# UKU207xx_power_board.net
KiCad netlist of a schematic drawn in Altium Designer
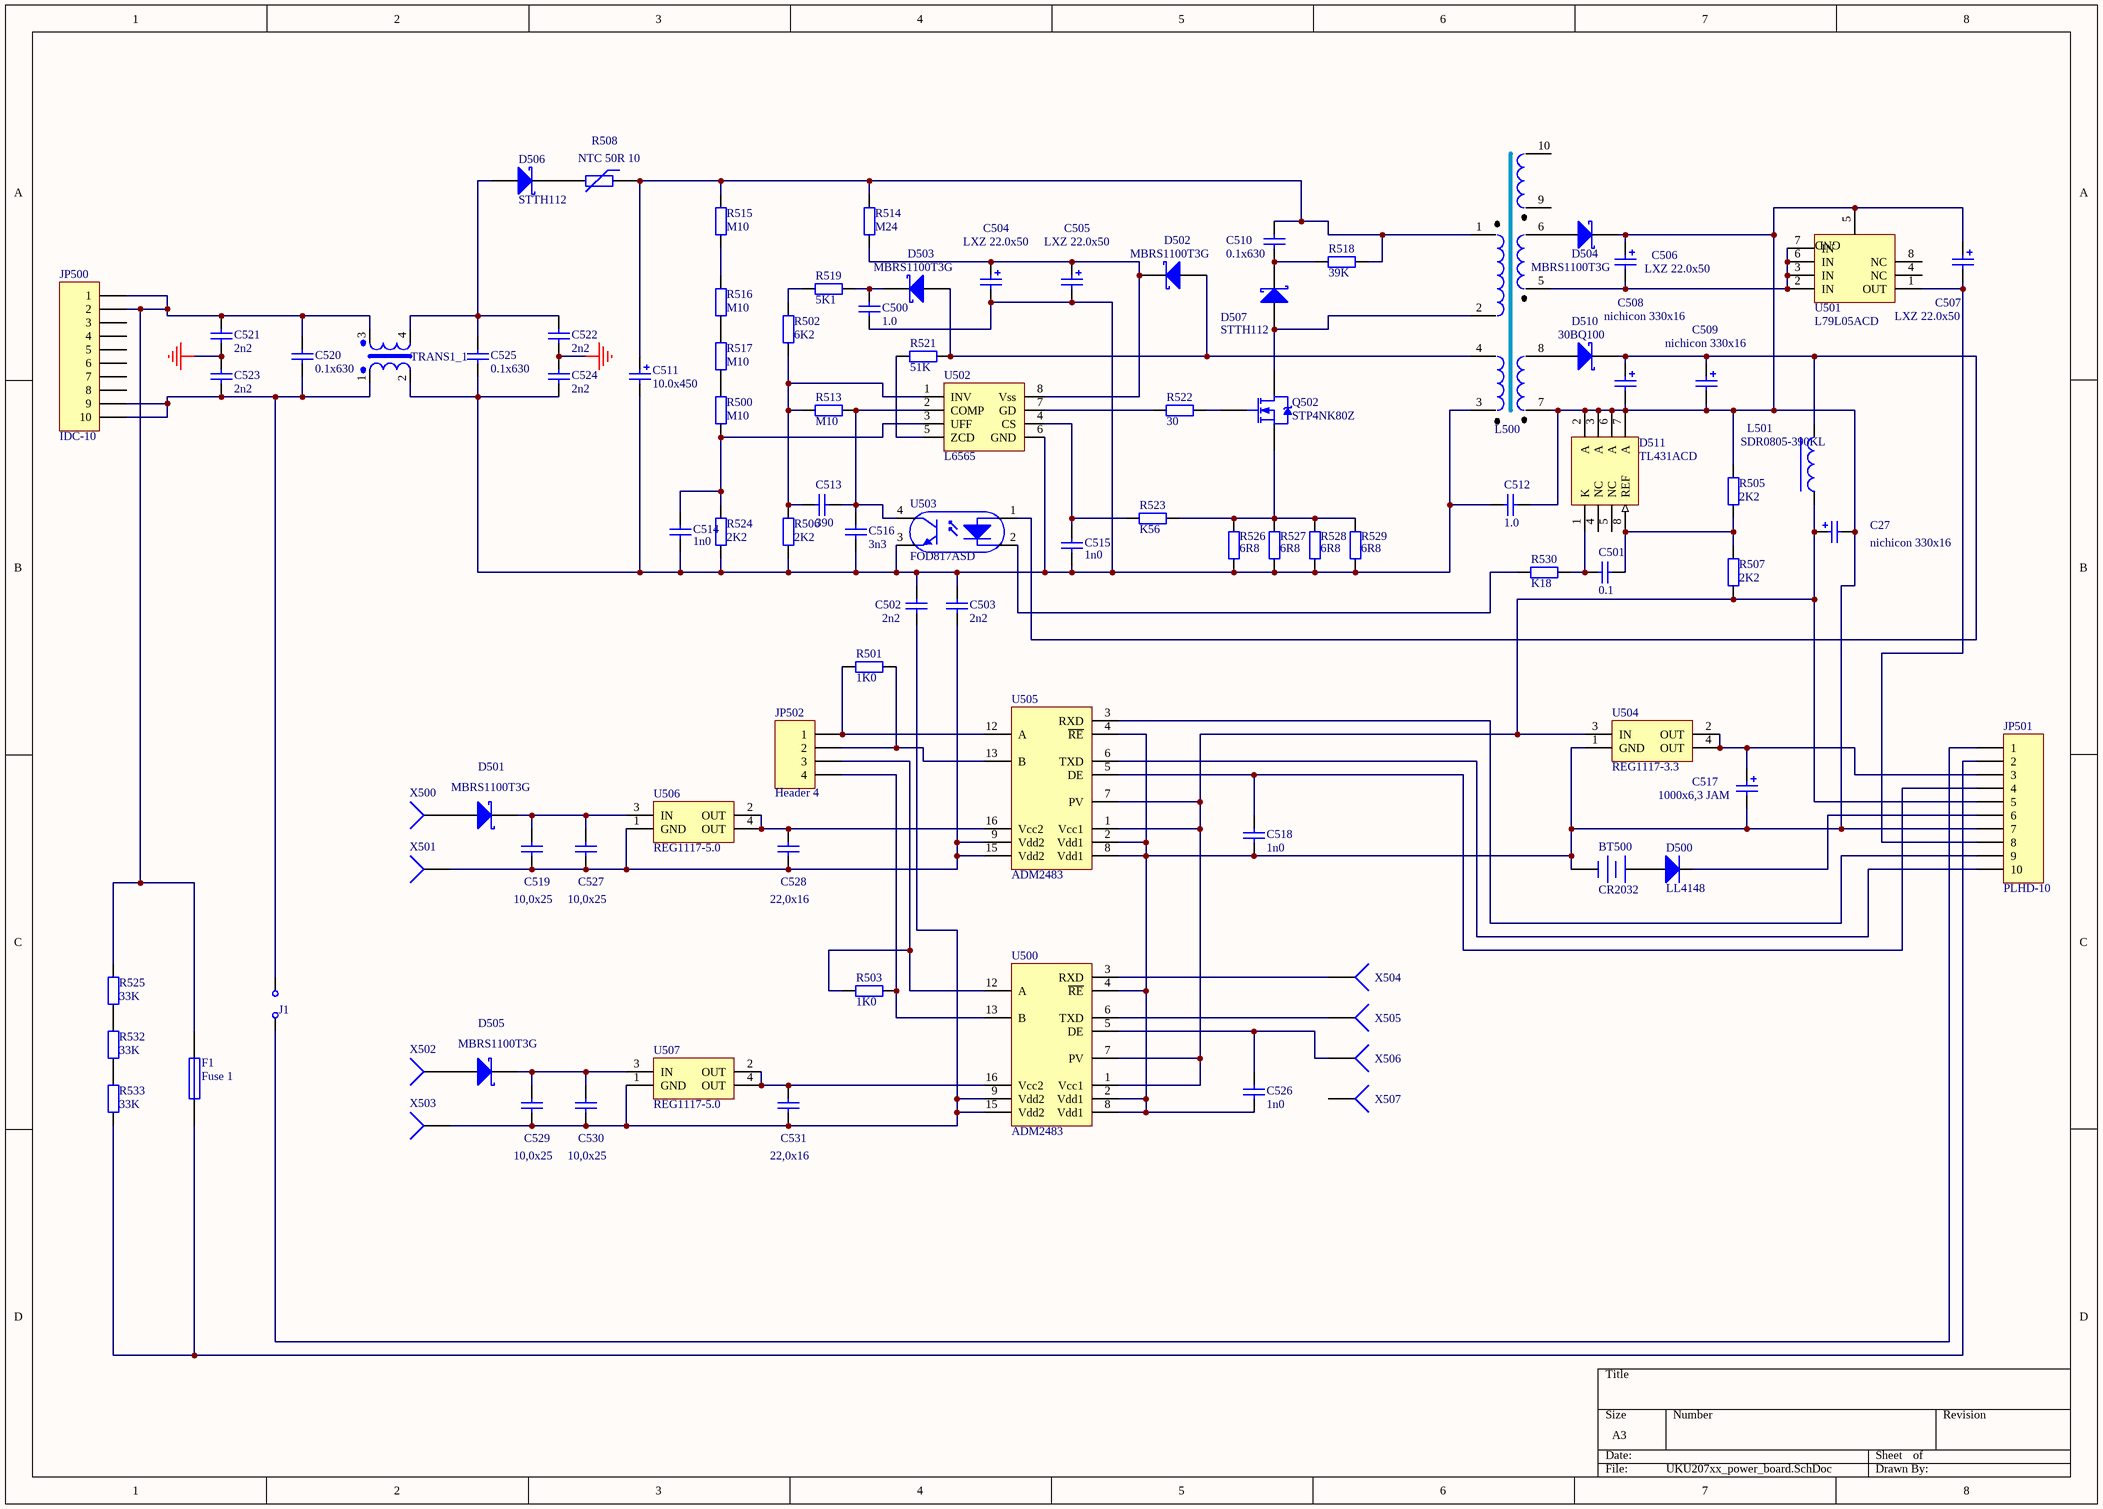
[diagram p0: UKU207xx_power_board.SchDoc]

(export (version "E")
  (design (tool "Eeschema 10.0.6"))
  (components
    (comp (ref "BT500")
      (value "CR2032")
      (footprint "BAT_HOLD_SMD")
      (description "Multicell Battery")
      (fields (field (name "MANUFACTURER") "Generic Components") (field (name "PUBLISHER") "Altium Limited"))
      (libsource (lib "Miscellaneous Devices") (part "Battery"))
    )
    (comp (ref "C27")
      (value "nichicon 330x16")
      (footprint "el3")
      (description "Polarized Capacitor (Radial)")
      (fields (field (name "MANUFACTURER") "Generic Components") (field (name "PUBLISHER") "Altium Limited"))
      (libsource (lib "PAL") (part "Cap Pol1"))
    )
    (comp (ref "C500")
      (value "1.0")
      (footprint "_1206")
      (description "Capacitor (Semiconductor SIM Model)")
      (fields (field (name "MANUFACTURER") "Generic Components") (field (name "PUBLISHER") "Altium Limited"))
      (libsource (lib "Miscellaneous Devices") (part "Cap Semi"))
    )
    (comp (ref "C501")
      (value "0.1")
      (footprint "_1206")
      (description "Capacitor (Semiconductor SIM Model)")
      (fields (field (name "MANUFACTURER") "Generic Components") (field (name "PUBLISHER") "Altium Limited"))
      (libsource (lib "Miscellaneous Devices") (part "Cap Semi"))
    )
    (comp (ref "C502")
      (value "2n2")
      (footprint "C8")
      (description "Capacitor (Semiconductor SIM Model)")
      (fields (field (name "MANUFACTURER") "Generic Components") (field (name "PUBLISHER") "Altium Limited"))
      (libsource (lib "Miscellaneous Devices") (part "Cap Semi"))
    )
    (comp (ref "C503")
      (value "2n2")
      (footprint "C8")
      (description "Capacitor (Semiconductor SIM Model)")
      (fields (field (name "MANUFACTURER") "Generic Components") (field (name "PUBLISHER") "Altium Limited"))
      (libsource (lib "Miscellaneous Devices") (part "Cap Semi"))
    )
    (comp (ref "C504")
      (value "LXZ 22.0x50")
      (footprint "el3")
      (description "Polarized Capacitor (Radial)")
      (fields (field (name "MANUFACTURER") "Generic Components") (field (name "PUBLISHER") "Altium Limited"))
      (libsource (lib "PAL") (part "Cap Pol1"))
    )
    (comp (ref "C505")
      (value "LXZ 22.0x50")
      (footprint "el3")
      (description "Polarized Capacitor (Radial)")
      (fields (field (name "MANUFACTURER") "Generic Components") (field (name "PUBLISHER") "Altium Limited"))
      (libsource (lib "PAL") (part "Cap Pol1"))
    )
    (comp (ref "C506")
      (value "LXZ 22.0x50")
      (footprint "el3")
      (description "Polarized Capacitor (Radial)")
      (fields (field (name "MANUFACTURER") "Generic Components") (field (name "PUBLISHER") "Altium Limited"))
      (libsource (lib "PAL") (part "Cap Pol1"))
    )
    (comp (ref "C507")
      (value "LXZ 22.0x50")
      (footprint "el3")
      (description "Polarized Capacitor (Radial)")
      (fields (field (name "MANUFACTURER") "Generic Components") (field (name "PUBLISHER") "Altium Limited"))
      (libsource (lib "PAL") (part "Cap Pol1"))
    )
    (comp (ref "C508")
      (value "nichicon 330x16")
      (footprint "el3")
      (description "Polarized Capacitor (Radial)")
      (fields (field (name "MANUFACTURER") "Generic Components") (field (name "PUBLISHER") "Altium Limited"))
      (libsource (lib "PAL") (part "Cap Pol1"))
    )
    (comp (ref "C509")
      (value "nichicon 330x16")
      (footprint "el3")
      (description "Polarized Capacitor (Radial)")
      (fields (field (name "MANUFACTURER") "Generic Components") (field (name "PUBLISHER") "Altium Limited"))
      (libsource (lib "PAL") (part "Cap Pol1"))
    )
    (comp (ref "C510")
      (value "0.1x630")
      (footprint "c15")
      (description "Capacitor (Semiconductor SIM Model)")
      (fields (field (name "MANUFACTURER") "Generic Components") (field (name "PUBLISHER") "Altium Limited"))
      (libsource (lib "Miscellaneous Devices") (part "Cap Semi"))
    )
    (comp (ref "C511")
      (value "10.0x450")
      (footprint "el_15_25_h")
      (description "Polarized Capacitor (Radial)")
      (fields (field (name "MANUFACTURER") "Generic Components") (field (name "PUBLISHER") "Altium Limited"))
      (libsource (lib "PAL") (part "Cap Pol1"))
    )
    (comp (ref "C512")
      (value "1.0")
      (footprint "C8")
      (description "Capacitor (Semiconductor SIM Model)")
      (fields (field (name "MANUFACTURER") "Generic Components") (field (name "PUBLISHER") "Altium Limited"))
      (libsource (lib "Miscellaneous Devices") (part "Cap Semi"))
    )
    (comp (ref "C513")
      (value "390")
      (footprint "_1206")
      (description "Capacitor (Semiconductor SIM Model)")
      (fields (field (name "MANUFACTURER") "Generic Components") (field (name "PUBLISHER") "Altium Limited"))
      (libsource (lib "Miscellaneous Devices") (part "Cap Semi"))
    )
    (comp (ref "C514")
      (value "1n0")
      (footprint "_1206")
      (description "Capacitor (Semiconductor SIM Model)")
      (fields (field (name "MANUFACTURER") "Generic Components") (field (name "PUBLISHER") "Altium Limited"))
      (libsource (lib "Miscellaneous Devices") (part "Cap Semi"))
    )
    (comp (ref "C515")
      (value "1n0")
      (footprint "_1206")
      (description "Capacitor (Semiconductor SIM Model)")
      (fields (field (name "MANUFACTURER") "Generic Components") (field (name "PUBLISHER") "Altium Limited"))
      (libsource (lib "Miscellaneous Devices") (part "Cap Semi"))
    )
    (comp (ref "C516")
      (value "3n3")
      (footprint "_1206")
      (description "Capacitor (Semiconductor SIM Model)")
      (fields (field (name "MANUFACTURER") "Generic Components") (field (name "PUBLISHER") "Altium Limited"))
      (libsource (lib "Miscellaneous Devices") (part "Cap Semi"))
    )
    (comp (ref "C517")
      (value "1000x6,3 JAM")
      (footprint "el5")
      (description "Polarized Capacitor (Radial)")
      (fields (field (name "MANUFACTURER") "Generic Components") (field (name "PUBLISHER") "Altium Limited"))
      (libsource (lib "PAL") (part "Cap Pol1"))
    )
    (comp (ref "C518")
      (value "1n0")
      (footprint "_1206")
      (description "Capacitor (Semiconductor SIM Model)")
      (fields (field (name "MANUFACTURER") "Generic Components") (field (name "PUBLISHER") "Altium Limited"))
      (libsource (lib "Miscellaneous Devices") (part "Cap Semi"))
    )
    (comp (ref "C519")
      (value "1.0")
      (footprint "_1206")
      (description "Capacitor (Semiconductor SIM Model)")
      (fields
        (field (name "MANUFACTURER") "Generic Components")
        (field (name "ALTIUM_VALUE") "10,0x25")
        (field (name "PUBLISHER") "Altium Limited")
      )
      (libsource (lib "Miscellaneous Devices") (part "Cap Semi"))
    )
    (comp (ref "C520")
      (value "0.1x630")
      (footprint "c15")
      (description "Capacitor (Semiconductor SIM Model)")
      (fields (field (name "MANUFACTURER") "Generic Components") (field (name "PUBLISHER") "Altium Limited"))
      (libsource (lib "Miscellaneous Devices") (part "Cap Semi"))
    )
    (comp (ref "C521")
      (value "2n2")
      (footprint "C8")
      (description "Capacitor (Semiconductor SIM Model)")
      (fields (field (name "MANUFACTURER") "Generic Components") (field (name "PUBLISHER") "Altium Limited"))
      (libsource (lib "Miscellaneous Devices") (part "Cap Semi"))
    )
    (comp (ref "C522")
      (value "2n2")
      (footprint "c8")
      (description "Capacitor (Semiconductor SIM Model)")
      (fields (field (name "MANUFACTURER") "Generic Components") (field (name "PUBLISHER") "Altium Limited"))
      (libsource (lib "Miscellaneous Devices") (part "Cap Semi"))
    )
    (comp (ref "C523")
      (value "2n2")
      (footprint "c8")
      (description "Capacitor (Semiconductor SIM Model)")
      (fields (field (name "MANUFACTURER") "Generic Components") (field (name "PUBLISHER") "Altium Limited"))
      (libsource (lib "Miscellaneous Devices") (part "Cap Semi"))
    )
    (comp (ref "C524")
      (value "2n2")
      (footprint "c8")
      (description "Capacitor (Semiconductor SIM Model)")
      (fields (field (name "MANUFACTURER") "Generic Components") (field (name "PUBLISHER") "Altium Limited"))
      (libsource (lib "Miscellaneous Devices") (part "Cap Semi"))
    )
    (comp (ref "C525")
      (value "0.1х630")
      (footprint "c15")
      (description "Capacitor (Semiconductor SIM Model)")
      (fields (field (name "MANUFACTURER") "Generic Components") (field (name "PUBLISHER") "Altium Limited"))
      (libsource (lib "Miscellaneous Devices") (part "Cap Semi"))
    )
    (comp (ref "C526")
      (value "1n0")
      (footprint "_1206")
      (description "Capacitor (Semiconductor SIM Model)")
      (fields (field (name "MANUFACTURER") "Generic Components") (field (name "PUBLISHER") "Altium Limited"))
      (libsource (lib "Miscellaneous Devices") (part "Cap Semi"))
    )
    (comp (ref "C527")
      (value "1.0")
      (footprint "_1206")
      (description "Capacitor (Semiconductor SIM Model)")
      (fields
        (field (name "MANUFACTURER") "Generic Components")
        (field (name "ALTIUM_VALUE") "10,0x25")
        (field (name "PUBLISHER") "Altium Limited")
      )
      (libsource (lib "Miscellaneous Devices") (part "Cap Semi"))
    )
    (comp (ref "C528")
      (value "1.0")
      (footprint "_1206")
      (description "Capacitor (Semiconductor SIM Model)")
      (fields
        (field (name "MANUFACTURER") "Generic Components")
        (field (name "ALTIUM_VALUE") "22,0x16")
        (field (name "PUBLISHER") "Altium Limited")
      )
      (libsource (lib "Miscellaneous Devices") (part "Cap Semi"))
    )
    (comp (ref "C529")
      (value "1.0")
      (footprint "_1206")
      (description "Capacitor (Semiconductor SIM Model)")
      (fields
        (field (name "MANUFACTURER") "Generic Components")
        (field (name "ALTIUM_VALUE") "10,0x25")
        (field (name "PUBLISHER") "Altium Limited")
      )
      (libsource (lib "Miscellaneous Devices") (part "Cap Semi"))
    )
    (comp (ref "C530")
      (value "1.0")
      (footprint "_1206")
      (description "Capacitor (Semiconductor SIM Model)")
      (fields
        (field (name "MANUFACTURER") "Generic Components")
        (field (name "ALTIUM_VALUE") "10,0x25")
        (field (name "PUBLISHER") "Altium Limited")
      )
      (libsource (lib "Miscellaneous Devices") (part "Cap Semi"))
    )
    (comp (ref "C531")
      (value "1.0")
      (footprint "_1206")
      (description "Capacitor (Semiconductor SIM Model)")
      (fields
        (field (name "MANUFACTURER") "Generic Components")
        (field (name "ALTIUM_VALUE") "22,0x16")
        (field (name "PUBLISHER") "Altium Limited")
      )
      (libsource (lib "Miscellaneous Devices") (part "Cap Semi"))
    )
    (comp (ref "D500")
      (value "LL4148")
      (footprint "_1206d")
      (description "Default Diode")
      (fields (field (name "MANUFACTURER") "Generic Components") (field (name "PUBLISHER") "Altium Limited"))
      (libsource (lib "PAL") (part "Diode"))
    )
    (comp (ref "D501")
      (value "MBRS1100T3G")
      (footprint "D_6_3")
      (description "Schottky Rectifier")
      (fields
        (field (name "MANUFACTURER") "International Rectifier")
        (field (name "PUBLISHER") "Altium Limited")
      )
      (libsource (lib "IR Discrete Diode") (part "10BQ015"))
    )
    (comp (ref "D502")
      (value "MBRS1100T3G")
      (footprint "D_6_3")
      (description "Schottky Rectifier")
      (fields
        (field (name "MANUFACTURER") "International Rectifier")
        (field (name "PUBLISHER") "Altium Limited")
      )
      (libsource (lib "IR Discrete Diode") (part "10BQ015"))
    )
    (comp (ref "D503")
      (value "MBRS1100T3G")
      (footprint "D_6_3")
      (description "Schottky Rectifier")
      (fields
        (field (name "MANUFACTURER") "International Rectifier")
        (field (name "PUBLISHER") "Altium Limited")
      )
      (libsource (lib "IR Discrete Diode") (part "10BQ015"))
    )
    (comp (ref "D504")
      (value "MBRS1100T3G")
      (footprint "D_6_3")
      (description "Schottky Rectifier")
      (fields
        (field (name "MANUFACTURER") "International Rectifier")
        (field (name "PUBLISHER") "Altium Limited")
      )
      (libsource (lib "IR Discrete Diode") (part "10BQ015"))
    )
    (comp (ref "D505")
      (value "MBRS1100T3G")
      (footprint "D_6_3")
      (description "Schottky Rectifier")
      (fields
        (field (name "MANUFACTURER") "International Rectifier")
        (field (name "PUBLISHER") "Altium Limited")
      )
      (libsource (lib "IR Discrete Diode") (part "10BQ015"))
    )
    (comp (ref "D506")
      (value "STTH112")
      (footprint "D_6_3")
      (description "Schottky Diode")
      (fields
        (field (name "MANUFACTURER") "International Rectifier")
        (field (name "PUBLISHER") "Altium Limited")
      )
      (libsource (lib "IR Discrete Diode") (part "10BQ015"))
    )
    (comp (ref "D507")
      (value "STTH112")
      (footprint "D_6_3")
      (description "Schottky Diode")
      (fields
        (field (name "MANUFACTURER") "International Rectifier")
        (field (name "PUBLISHER") "Altium Limited")
      )
      (libsource (lib "IR Discrete Diode") (part "10BQ015"))
    )
    (comp (ref "D510")
      (value "30BQ100")
      (footprint "30BQ100")
      (description "Schottky Rectifier")
      (fields
        (field (name "MANUFACTURER") "International Rectifier")
        (field (name "PUBLISHER") "Altium Limited")
      )
      (libsource (lib "IR Discrete Diode") (part "10BQ015"))
    )
    (comp (ref "D511")
      (value "TL431ACD")
      (footprint "SO-G8")
      (description "Programmable Precision Reference")
      (fields (field (name "MANUFACTURER") "Motorola") (field (name "PUBLISHER") "Altium Limited"))
      (libsource (lib "Motorola Power Management Voltage Reference") (part "TL431ACD"))
    )
    (comp (ref "F1")
      (value "Fuse 1")
      (footprint "PIN-W2/E2.8")
      (description "Fuse")
      (fields (field (name "MANUFACTURER") "Generic Components") (field (name "PUBLISHER") "Altium Limited"))
      (libsource (lib "Miscellaneous Devices") (part "Fuse 1"))
    )
    (comp (ref "J1")
      (value "~")
      (footprint "BT5-2")
      (description "Switch")
      (fields (field (name "MANUFACTURER") "Generic Components") (field (name "PUBLISHER") "Altium Limited"))
      (libsource (lib "PAL") (part "JMP"))
    )
    (comp (ref "JP500")
      (value "IDC-10")
      (footprint "HDR2X5")
      (description "Header, 10-Pin")
      (fields (field (name "MANUFACTURER") "Generic Components") (field (name "PUBLISHER") "Altium Limited"))
      (libsource (lib "") (part "Header 10_1"))
    )
    (comp (ref "JP501")
      (value "PLHD-10")
      (footprint "HDR2X5")
      (description "Header, 10-Pin")
      (fields (field (name "MANUFACTURER") "Generic Components") (field (name "PUBLISHER") "Altium Limited"))
      (libsource (lib "Miscellaneous Connectors") (part "Header 10"))
    )
    (comp (ref "JP502")
      (value "Header 4")
      (footprint "PAL:2EDG-5.08-4")
      (description "Header, 4-Pin")
      (fields (field (name "MANUFACTURER") "Generic Components") (field (name "PUBLISHER") "Altium Limited"))
      (libsource (lib "Miscellaneous Connectors") (part "Header 4"))
    )
    (comp (ref "L500")
      (value "L220-K10")
      (footprint "trans_ring1")
      (description "Дроссель")
      (libsource (lib "PAL") (part "L1_dc_2"))
    )
    (comp (ref "L501")
      (value "SDR0805-390KL")
      (footprint "L10x10")
      (description "Magnetic-Core Inductor")
      (fields (field (name "MANUFACTURER") "Generic Components") (field (name "PUBLISHER") "Altium Limited"))
      (libsource (lib "PAL") (part "Inductor Konstr 2"))
    )
    (comp (ref "Q502")
      (value "STP4NK80Z")
      (footprint "TO220_h")
      (description "N-Channel Power MOSFET")
      (fields (field (name "MANUFACTURER") "Generic Components") (field (name "PUBLISHER") "Altium Limited"))
      (libsource (lib "Miscellaneous Devices") (part "NMOS-2"))
    )
    (comp (ref "R500")
      (value "M10")
      (footprint "_1206")
      (description "Resistor")
      (fields (field (name "MANUFACTURER") "Generic Components") (field (name "PUBLISHER") "Altium Limited"))
      (libsource (lib "Miscellaneous Devices") (part "Res2"))
    )
    (comp (ref "R501")
      (value "1K0")
      (footprint "_1206")
      (description "Resistor")
      (fields (field (name "MANUFACTURER") "Generic Components") (field (name "PUBLISHER") "Altium Limited"))
      (libsource (lib "") (part "Res2_2"))
    )
    (comp (ref "R502")
      (value "6K2")
      (footprint "_1206")
      (description "Resistor")
      (fields (field (name "MANUFACTURER") "Generic Components") (field (name "PUBLISHER") "Altium Limited"))
      (libsource (lib "Miscellaneous Devices") (part "Res2"))
    )
    (comp (ref "R503")
      (value "1K0")
      (footprint "_1206")
      (description "Resistor")
      (fields (field (name "MANUFACTURER") "Generic Components") (field (name "PUBLISHER") "Altium Limited"))
      (libsource (lib "") (part "Res2_2"))
    )
    (comp (ref "R505")
      (value "2K2")
      (footprint "_1206")
      (description "Resistor")
      (fields (field (name "MANUFACTURER") "Generic Components") (field (name "PUBLISHER") "Altium Limited"))
      (libsource (lib "Miscellaneous Devices") (part "Res2"))
    )
    (comp (ref "R506")
      (value "2K2")
      (footprint "_1206")
      (description "Resistor")
      (fields (field (name "MANUFACTURER") "Generic Components") (field (name "PUBLISHER") "Altium Limited"))
      (libsource (lib "Miscellaneous Devices") (part "Res2"))
    )
    (comp (ref "R507")
      (value "2K2")
      (footprint "_1206")
      (description "Resistor")
      (fields (field (name "MANUFACTURER") "Generic Components") (field (name "PUBLISHER") "Altium Limited"))
      (libsource (lib "Miscellaneous Devices") (part "Res2"))
    )
    (comp (ref "R508")
      (value "NTC 50R 10")
      (footprint "JVR07N")
      (description "Varistor (Voltage-Sensitive Resistor)")
      (fields (field (name "MANUFACTURER") "Generic Components") (field (name "PUBLISHER") "Altium Limited"))
      (libsource (lib "Miscellaneous Devices") (part "Res Varistor"))
    )
    (comp (ref "R513")
      (value "M10")
      (footprint "_1206")
      (description "Resistor")
      (fields (field (name "MANUFACTURER") "Generic Components") (field (name "PUBLISHER") "Altium Limited"))
      (libsource (lib "") (part "Res2_2"))
    )
    (comp (ref "R514")
      (value "M24")
      (footprint "AXIAL-0.7")
      (description "Resistor")
      (fields (field (name "MANUFACTURER") "Generic Components") (field (name "PUBLISHER") "Altium Limited"))
      (libsource (lib "Miscellaneous Devices") (part "Res2"))
    )
    (comp (ref "R515")
      (value "M10")
      (footprint "_1206")
      (description "Resistor")
      (fields (field (name "MANUFACTURER") "Generic Components") (field (name "PUBLISHER") "Altium Limited"))
      (libsource (lib "Miscellaneous Devices") (part "Res2"))
    )
    (comp (ref "R516")
      (value "M10")
      (footprint "_1206")
      (description "Resistor")
      (fields (field (name "MANUFACTURER") "Generic Components") (field (name "PUBLISHER") "Altium Limited"))
      (libsource (lib "Miscellaneous Devices") (part "Res2"))
    )
    (comp (ref "R517")
      (value "M10")
      (footprint "_1206")
      (description "Resistor")
      (fields (field (name "MANUFACTURER") "Generic Components") (field (name "PUBLISHER") "Altium Limited"))
      (libsource (lib "Miscellaneous Devices") (part "Res2"))
    )
    (comp (ref "R518")
      (value "39K")
      (footprint "AXIAL-0.7")
      (description "Resistor")
      (fields (field (name "MANUFACTURER") "Generic Components") (field (name "PUBLISHER") "Altium Limited"))
      (libsource (lib "") (part "Res2_2"))
    )
    (comp (ref "R519")
      (value "5K1")
      (footprint "_1206")
      (description "Resistor")
      (fields (field (name "MANUFACTURER") "Generic Components") (field (name "PUBLISHER") "Altium Limited"))
      (libsource (lib "") (part "Res2_2"))
    )
    (comp (ref "R521")
      (value "51K")
      (footprint "_1206")
      (description "Resistor")
      (fields (field (name "MANUFACTURER") "Generic Components") (field (name "PUBLISHER") "Altium Limited"))
      (libsource (lib "") (part "Res2_2"))
    )
    (comp (ref "R522")
      (value "30")
      (footprint "_1206")
      (description "Resistor")
      (fields (field (name "MANUFACTURER") "Generic Components") (field (name "PUBLISHER") "Altium Limited"))
      (libsource (lib "") (part "Res2_2"))
    )
    (comp (ref "R523")
      (value "K56")
      (footprint "_1206")
      (description "Resistor")
      (fields (field (name "MANUFACTURER") "Generic Components") (field (name "PUBLISHER") "Altium Limited"))
      (libsource (lib "") (part "Res2_2"))
    )
    (comp (ref "R524")
      (value "2K2")
      (footprint "_1206")
      (description "Resistor")
      (fields (field (name "MANUFACTURER") "Generic Components") (field (name "PUBLISHER") "Altium Limited"))
      (libsource (lib "Miscellaneous Devices") (part "Res2"))
    )
    (comp (ref "R525")
      (value "33K")
      (footprint "_1206")
      (description "Resistor")
      (fields (field (name "MANUFACTURER") "Generic Components") (field (name "PUBLISHER") "Altium Limited"))
      (libsource (lib "Miscellaneous Devices") (part "Res2"))
    )
    (comp (ref "R526")
      (value "6R8")
      (footprint "_1206")
      (description "Resistor")
      (fields (field (name "MANUFACTURER") "Generic Components") (field (name "PUBLISHER") "Altium Limited"))
      (libsource (lib "") (part "Res2_1"))
    )
    (comp (ref "R527")
      (value "6R8")
      (footprint "_1206")
      (description "Resistor")
      (fields (field (name "MANUFACTURER") "Generic Components") (field (name "PUBLISHER") "Altium Limited"))
      (libsource (lib "") (part "Res2_1"))
    )
    (comp (ref "R528")
      (value "6R8")
      (footprint "_1206")
      (description "Resistor")
      (fields (field (name "MANUFACTURER") "Generic Components") (field (name "PUBLISHER") "Altium Limited"))
      (libsource (lib "") (part "Res2_1"))
    )
    (comp (ref "R529")
      (value "6R8")
      (footprint "_1206")
      (description "Resistor")
      (fields (field (name "MANUFACTURER") "Generic Components") (field (name "PUBLISHER") "Altium Limited"))
      (libsource (lib "") (part "Res2_1"))
    )
    (comp (ref "R530")
      (value "K18")
      (footprint "_1206")
      (description "Resistor")
      (fields (field (name "MANUFACTURER") "Generic Components") (field (name "PUBLISHER") "Altium Limited"))
      (libsource (lib "") (part "Res2_2"))
    )
    (comp (ref "R532")
      (value "33K")
      (footprint "_1206")
      (description "Resistor")
      (fields (field (name "MANUFACTURER") "Generic Components") (field (name "PUBLISHER") "Altium Limited"))
      (libsource (lib "Miscellaneous Devices") (part "Res2"))
    )
    (comp (ref "R533")
      (value "33K")
      (footprint "_1206")
      (description "Resistor")
      (fields (field (name "MANUFACTURER") "Generic Components") (field (name "PUBLISHER") "Altium Limited"))
      (libsource (lib "Miscellaneous Devices") (part "Res2"))
    )
    (comp (ref "T500")
      (value "TRANS1_1")
      (footprint "3030R4")
      (fields (field (name "MANUFACTURER") "Generic Components") (field (name "PUBLISHER") "Altium Limited"))
      (libsource (lib "PAL") (part "TRANS1_1"))
    )
    (comp (ref "U500") (value "ADM2483") (footprint "SO-G16/D10.4") (libsource (lib "PAL") (part "ADM2483")))
    (comp (ref "U501")
      (value "L79L05ACD")
      (footprint "SO-G8")
      (description "Negative Voltage Regulator")
      (fields (field (name "MANUFACTURER") "ST-Microelectronics") (field (name "PUBLISHER") "Altium Limited"))
      (libsource (lib "ST Power Mgt Voltage Regulator") (part "L79L05ACD"))
    )
    (comp (ref "U502") (value "L6565") (footprint "so-g8") (libsource (lib "PAL") (part "L6565")))
    (comp (ref "U503") (value "FOD817ASD") (footprint "FOD817ASD") (libsource (lib "PAL") (part "F00817ASD")))
    (comp (ref "U504")
      (value "REG1117-3.3")
      (footprint "DSO-G3")
      (description "800mA and 1A Low Dropout Positive Regulator 2.85V, 3.3V, 5V, and Adjustable")
      (fields (field (name "MANUFACTURER") "Burr-Brown") (field (name "PUBLISHER") "Altium Limited"))
      (libsource (lib "BB Power Mgt Voltage Regulator") (part "REG1117-3.3"))
    )
    (comp (ref "U505") (value "ADM2483") (footprint "SO-G16/D10.4") (libsource (lib "PAL") (part "ADM2483")))
    (comp (ref "U506")
      (value "REG1117-5.0")
      (footprint "DSO-G3")
      (description "800mA and 1A Low Dropout Positive Regulator 2.85V, 3.3V, 5V, and Adjustable")
      (fields (field (name "MANUFACTURER") "Burr-Brown") (field (name "PUBLISHER") "Altium Limited"))
      (libsource (lib "BB Power Mgt Voltage Regulator") (part "REG1117-3.3"))
    )
    (comp (ref "U507")
      (value "REG1117-5.0")
      (footprint "DSO-G3")
      (description "800mA and 1A Low Dropout Positive Regulator 2.85V, 3.3V, 5V, and Adjustable")
      (fields (field (name "MANUFACTURER") "Burr-Brown") (field (name "PUBLISHER") "Altium Limited"))
      (libsource (lib "BB Power Mgt Voltage Regulator") (part "REG1117-3.3"))
    )
    (comp (ref "X500")
      (value "Socket")
      (footprint "PIN1")
      (fields (field (name "MANUFACTURER") "Generic Components") (field (name "PUBLISHER") "Altium Limited"))
      (libsource (lib "Miscellaneous Connectors") (part "Socket"))
    )
    (comp (ref "X501")
      (value "Socket")
      (footprint "PIN1")
      (fields (field (name "MANUFACTURER") "Generic Components") (field (name "PUBLISHER") "Altium Limited"))
      (libsource (lib "Miscellaneous Connectors") (part "Socket"))
    )
    (comp (ref "X502")
      (value "Socket")
      (footprint "PIN1")
      (fields (field (name "MANUFACTURER") "Generic Components") (field (name "PUBLISHER") "Altium Limited"))
      (libsource (lib "Miscellaneous Connectors") (part "Socket"))
    )
    (comp (ref "X503")
      (value "Socket")
      (footprint "PIN1")
      (fields (field (name "MANUFACTURER") "Generic Components") (field (name "PUBLISHER") "Altium Limited"))
      (libsource (lib "Miscellaneous Connectors") (part "Socket"))
    )
    (comp (ref "X504")
      (value "Socket")
      (footprint "PIN1")
      (fields (field (name "MANUFACTURER") "Generic Components") (field (name "PUBLISHER") "Altium Limited"))
      (libsource (lib "Miscellaneous Connectors") (part "Socket"))
    )
    (comp (ref "X505")
      (value "Socket")
      (footprint "PIN1")
      (fields (field (name "MANUFACTURER") "Generic Components") (field (name "PUBLISHER") "Altium Limited"))
      (libsource (lib "Miscellaneous Connectors") (part "Socket"))
    )
    (comp (ref "X506")
      (value "Socket")
      (footprint "PIN1")
      (fields (field (name "MANUFACTURER") "Generic Components") (field (name "PUBLISHER") "Altium Limited"))
      (libsource (lib "Miscellaneous Connectors") (part "Socket"))
    )
    (comp (ref "X507")
      (value "Socket")
      (footprint "PIN1")
      (fields (field (name "MANUFACTURER") "Generic Components") (field (name "PUBLISHER") "Altium Limited"))
      (libsource (lib "Miscellaneous Connectors") (part "Socket"))
    )
  )
  (nets
    (net (code "1") (name "GND_GND") (class "Default")
      (node (ref "C521") (pin "1") (pinfunction "1_1") (pintype "passive"))
      (node (ref "C522") (pin "1") (pinfunction "1_1") (pintype "passive"))
      (node (ref "C523") (pin "2") (pinfunction "2_2") (pintype "passive"))
      (node (ref "C524") (pin "2") (pinfunction "2_2") (pintype "passive"))
    )
    (net (code "2") (name "Net-(BT500-+)") (class "Default")
      (node (ref "BT500") (pin "1") (pinfunction "+_1") (pintype "passive"))
      (node (ref "D500") (pin "1") (pinfunction "A_1") (pintype "passive"))
    )
    (net (code "3") (name "Net-(BT500--)") (class "Default")
      (node (ref "BT500") (pin "2") (pinfunction "-_2") (pintype "passive"))
      (node (ref "C27") (pin "2") (pinfunction "2_2") (pintype "passive"))
      (node (ref "C506") (pin "1") (pinfunction "1_1") (pintype "passive"))
      (node (ref "C507") (pin "1") (pinfunction "1_1") (pintype "passive"))
      (node (ref "C508") (pin "2") (pinfunction "2_2") (pintype "passive"))
      (node (ref "C509") (pin "2") (pinfunction "2_2") (pintype "passive"))
      (node (ref "C512") (pin "1") (pinfunction "1_1") (pintype "passive"))
      (node (ref "C517") (pin "2") (pinfunction "2_2") (pintype "passive"))
      (node (ref "C518") (pin "1") (pinfunction "1_1") (pintype "passive"))
      (node (ref "C526") (pin "1") (pinfunction "1_1") (pintype "passive"))
      (node (ref "D504") (pin "2") (pinfunction "K_2") (pintype "passive"))
      (node (ref "D511") (pin "2") (pinfunction "A_2") (pintype "passive"))
      (node (ref "D511") (pin "3") (pinfunction "A_3") (pintype "passive"))
      (node (ref "D511") (pin "6") (pinfunction "A_6") (pintype "passive"))
      (node (ref "D511") (pin "7") (pinfunction "A_7") (pintype "passive"))
      (node (ref "JP501") (pin "7") (pinfunction "7_7") (pintype "passive"))
      (node (ref "L500") (pin "7") (pintype "passive"))
      (node (ref "R505") (pin "2") (pinfunction "2_2") (pintype "passive"))
      (node (ref "U500") (pin "2") (pinfunction "Vdd1_2") (pintype "passive"))
      (node (ref "U500") (pin "4") (pinfunction "~{RE}_4") (pintype "passive"))
      (node (ref "U500") (pin "8") (pinfunction "Vdd1_8") (pintype "passive"))
      (node (ref "U501") (pin "5") (pinfunction "GND_5") (pintype "power_in"))
      (node (ref "U504") (pin "1") (pinfunction "GND_1") (pintype "power_in"))
      (node (ref "U505") (pin "2") (pinfunction "Vdd1_2") (pintype "passive"))
      (node (ref "U505") (pin "4") (pinfunction "~{RE}_4") (pintype "passive"))
      (node (ref "U505") (pin "8") (pinfunction "Vdd1_8") (pintype "passive"))
    )
    (net (code "4") (name "Net-(C506-Pad2)") (class "Default")
      (node (ref "C506") (pin "2") (pinfunction "2_2") (pintype "passive"))
      (node (ref "L500") (pin "5") (pintype "passive"))
      (node (ref "U501") (pin "2") (pinfunction "IN_2") (pintype "power_in"))
      (node (ref "U501") (pin "3") (pinfunction "IN_3") (pintype "power_in"))
      (node (ref "U501") (pin "6") (pinfunction "IN_6") (pintype "power_in"))
      (node (ref "U501") (pin "7") (pinfunction "IN_7") (pintype "power_in"))
    )
    (net (code "5") (name "Net-(C510-Pad2)") (class "Default")
      (node (ref "C510") (pin "2") (pinfunction "2_2") (pintype "passive"))
      (node (ref "C511") (pin "1") (pinfunction "1_1") (pintype "passive"))
      (node (ref "L500") (pin "1") (pintype "passive"))
      (node (ref "R508") (pin "1") (pinfunction "1_1") (pintype "passive"))
      (node (ref "R514") (pin "2") (pinfunction "2_2") (pintype "passive"))
      (node (ref "R515") (pin "2") (pinfunction "2_2") (pintype "passive"))
      (node (ref "R518") (pin "1") (pinfunction "1_1") (pintype "passive"))
    )
    (net (code "6") (name "Net-(C517-Pad1)") (class "Default")
      (node (ref "C517") (pin "1") (pinfunction "1_1") (pintype "passive"))
      (node (ref "JP501") (pin "3") (pinfunction "3_3") (pintype "passive"))
      (node (ref "U504") (pin "2") (pinfunction "OUT_2") (pintype "power_in"))
      (node (ref "U504") (pin "4") (pinfunction "OUT_4") (pintype "power_in"))
    )
    (net (code "7") (name "Net-(D500-K)") (class "Default")
      (node (ref "D500") (pin "2") (pinfunction "K_2") (pintype "passive"))
      (node (ref "JP501") (pin "6") (pinfunction "6_6") (pintype "passive"))
    )
    (net (code "8") (name "Net-(D501-A)") (class "Default")
      (node (ref "D501") (pin "1") (pinfunction "A_1") (pintype "passive"))
      (node (ref "X500") (pin "1") (pinfunction "1_1") (pintype "passive"))
    )
    (net (code "9") (name "Net-(D501-K)") (class "Default")
      (node (ref "C519") (pin "2") (pinfunction "2_2") (pintype "passive"))
      (node (ref "C527") (pin "2") (pinfunction "2_2") (pintype "passive"))
      (node (ref "D501") (pin "2") (pinfunction "K_2") (pintype "passive"))
      (node (ref "U506") (pin "3") (pinfunction "IN_3") (pintype "power_in"))
    )
    (net (code "10") (name "Net-(D502-A)") (class "Default")
      (node (ref "D502") (pin "1") (pinfunction "A_1") (pintype "passive"))
      (node (ref "D503") (pin "1") (pinfunction "A_1") (pintype "passive"))
      (node (ref "L500") (pin "4") (pintype "passive"))
      (node (ref "R521") (pin "1") (pinfunction "1_1") (pintype "passive"))
    )
    (net (code "11") (name "Net-(D502-K)") (class "Default")
      (node (ref "C504") (pin "1") (pinfunction "1_1") (pintype "passive"))
      (node (ref "C505") (pin "1") (pinfunction "1_1") (pintype "passive"))
      (node (ref "D502") (pin "2") (pinfunction "K_2") (pintype "passive"))
      (node (ref "R514") (pin "1") (pinfunction "1_1") (pintype "passive"))
      (node (ref "U502") (pin "8") (pinfunction "Vss_8") (pintype "passive"))
    )
    (net (code "12") (name "Net-(D503-K)") (class "Default")
      (node (ref "C500") (pin "2") (pinfunction "2_2") (pintype "passive"))
      (node (ref "D503") (pin "2") (pinfunction "K_2") (pintype "passive"))
      (node (ref "R519") (pin "1") (pinfunction "1_1") (pintype "passive"))
    )
    (net (code "13") (name "Net-(D504-A)") (class "Default")
      (node (ref "D504") (pin "1") (pinfunction "A_1") (pintype "passive"))
      (node (ref "L500") (pin "6") (pintype "passive"))
    )
    (net (code "14") (name "Net-(D505-A)") (class "Default")
      (node (ref "D505") (pin "1") (pinfunction "A_1") (pintype "passive"))
      (node (ref "X502") (pin "1") (pinfunction "1_1") (pintype "passive"))
    )
    (net (code "15") (name "Net-(D505-K)") (class "Default")
      (node (ref "C529") (pin "2") (pinfunction "2_2") (pintype "passive"))
      (node (ref "C530") (pin "2") (pinfunction "2_2") (pintype "passive"))
      (node (ref "D505") (pin "2") (pinfunction "K_2") (pintype "passive"))
      (node (ref "U507") (pin "3") (pinfunction "IN_3") (pintype "power_in"))
    )
    (net (code "16") (name "Net-(D506-A)") (class "Default")
      (node (ref "C522") (pin "2") (pinfunction "2_2") (pintype "passive"))
      (node (ref "C525") (pin "2") (pinfunction "2_2") (pintype "passive"))
      (node (ref "D506") (pin "1") (pinfunction "A_1") (pintype "passive"))
      (node (ref "T500") (pin "4") (pinfunction "Sec1-_4") (pintype "passive"))
    )
    (net (code "17") (name "Net-(D506-K)") (class "Default")
      (node (ref "D506") (pin "2") (pinfunction "K_2") (pintype "passive"))
      (node (ref "R508") (pin "2") (pinfunction "2_2") (pintype "passive"))
    )
    (net (code "18") (name "Net-(D507-A)") (class "Default")
      (node (ref "D507") (pin "1") (pinfunction "A_1") (pintype "passive"))
      (node (ref "L500") (pin "2") (pintype "passive"))
      (node (ref "Q502") (pin "2") (pinfunction "D_2") (pintype "passive"))
    )
    (net (code "19") (name "Net-(D507-K)") (class "Default")
      (node (ref "C510") (pin "1") (pinfunction "1_1") (pintype "passive"))
      (node (ref "D507") (pin "2") (pinfunction "K_2") (pintype "passive"))
      (node (ref "R518") (pin "2") (pinfunction "2_2") (pintype "passive"))
    )
    (net (code "20") (name "Net-(D510-A)") (class "Default")
      (node (ref "D510") (pin "1") (pinfunction "A_1") (pintype "passive"))
      (node (ref "L500") (pin "8") (pintype "passive"))
    )
    (net (code "21") (name "Net-(D510-K)") (class "Default")
      (node (ref "C508") (pin "1") (pinfunction "1_1") (pintype "passive"))
      (node (ref "C509") (pin "1") (pinfunction "1_1") (pintype "passive"))
      (node (ref "D510") (pin "2") (pinfunction "K_2") (pintype "passive"))
      (node (ref "L501") (pin "2") (pinfunction "2_2") (pintype "passive"))
      (node (ref "U503") (pin "1") (pinfunction "0_1") (pintype "passive"))
    )
    (net (code "22") (name "Net-(D511-K)") (class "Default")
      (node (ref "C501") (pin "2") (pinfunction "2_2") (pintype "passive"))
      (node (ref "D511") (pin "1") (pinfunction "K_1") (pintype "passive"))
      (node (ref "R530") (pin "1") (pinfunction "1_1") (pintype "passive"))
    )
    (net (code "23") (name "Net-(D511-REF)") (class "Default")
      (node (ref "C501") (pin "1") (pinfunction "1_1") (pintype "passive"))
      (node (ref "D511") (pin "8") (pinfunction "REF_8") (pintype "input"))
      (node (ref "R505") (pin "1") (pinfunction "1_1") (pintype "passive"))
      (node (ref "R507") (pin "2") (pinfunction "2_2") (pintype "passive"))
    )
    (net (code "24") (name "Net-(F1-Pad1)") (class "Default")
      (node (ref "F1") (pin "1") (pinfunction "1_1") (pintype "passive"))
      (node (ref "JP501") (pin "2") (pinfunction "2_2") (pintype "passive"))
      (node (ref "R533") (pin "1") (pinfunction "1_1") (pintype "passive"))
    )
    (net (code "25") (name "Net-(J1-Pad2)") (class "Default")
      (node (ref "J1") (pin "2") (pinfunction "2_2") (pintype "passive"))
      (node (ref "JP501") (pin "1") (pinfunction "1_1") (pintype "passive"))
    )
    (net (code "26") (name "Net-(Q502-G)") (class "Default")
      (node (ref "Q502") (pin "1") (pinfunction "G_1") (pintype "passive"))
      (node (ref "R522") (pin "1") (pinfunction "1_1") (pintype "passive"))
    )
    (net (code "27") (name "Net-(Q502-S)") (class "Default")
      (node (ref "Q502") (pin "3") (pinfunction "S_3") (pintype "passive"))
      (node (ref "R523") (pin "1") (pinfunction "1_1") (pintype "passive"))
      (node (ref "R526") (pin "1") (pinfunction "1_1") (pintype "passive"))
      (node (ref "R527") (pin "1") (pinfunction "1_1") (pintype "passive"))
      (node (ref "R528") (pin "1") (pinfunction "1_1") (pintype "passive"))
      (node (ref "R529") (pin "1") (pinfunction "1_1") (pintype "passive"))
    )
    (net (code "28") (name "Net-(R500-Pad2)") (class "Default")
      (node (ref "R500") (pin "2") (pinfunction "2_2") (pintype "passive"))
      (node (ref "R517") (pin "1") (pinfunction "1_1") (pintype "passive"))
    )
    (net (code "29") (name "Net-(R502-Pad2)") (class "Default")
      (node (ref "R502") (pin "2") (pinfunction "2_2") (pintype "passive"))
      (node (ref "R519") (pin "2") (pinfunction "2_2") (pintype "passive"))
    )
    (net (code "30") (name "Net-(R515-Pad1)") (class "Default")
      (node (ref "R515") (pin "1") (pinfunction "1_1") (pintype "passive"))
      (node (ref "R516") (pin "2") (pinfunction "2_2") (pintype "passive"))
    )
    (net (code "31") (name "Net-(R516-Pad1)") (class "Default")
      (node (ref "R516") (pin "1") (pinfunction "1_1") (pintype "passive"))
      (node (ref "R517") (pin "2") (pinfunction "2_2") (pintype "passive"))
    )
    (net (code "32") (name "Net-(R525-Pad1)") (class "Default")
      (node (ref "R525") (pin "1") (pinfunction "1_1") (pintype "passive"))
      (node (ref "R532") (pin "2") (pinfunction "2_2") (pintype "passive"))
    )
    (net (code "33") (name "Net-(R532-Pad1)") (class "Default")
      (node (ref "R532") (pin "1") (pinfunction "1_1") (pintype "passive"))
      (node (ref "R533") (pin "2") (pinfunction "2_2") (pintype "passive"))
    )
    (net (code "34") (name "Net-(T500-Pri+)") (class "Default")
      (node (ref "C520") (pin "1") (pinfunction "1_1") (pintype "passive"))
      (node (ref "C523") (pin "1") (pinfunction "1_1") (pintype "passive"))
      (node (ref "J1") (pin "1") (pinfunction "1_1") (pintype "passive"))
      (node (ref "JP500") (pin "10") (pinfunction "10_10") (pintype "passive"))
      (node (ref "JP500") (pin "9") (pinfunction "9_9") (pintype "passive"))
      (node (ref "T500") (pin "1") (pinfunction "Pri+_1") (pintype "passive"))
    )
    (net (code "35") (name "Net-(T500-Pri-)") (class "Default")
      (node (ref "C500") (pin "1") (pinfunction "1_1") (pintype "passive"))
      (node (ref "C502") (pin "2") (pinfunction "2_2") (pintype "passive"))
      (node (ref "C503") (pin "2") (pinfunction "2_2") (pintype "passive"))
      (node (ref "C504") (pin "2") (pinfunction "2_2") (pintype "passive"))
      (node (ref "C505") (pin "2") (pinfunction "2_2") (pintype "passive"))
      (node (ref "C511") (pin "2") (pinfunction "2_2") (pintype "passive"))
      (node (ref "C512") (pin "2") (pinfunction "2_2") (pintype "passive"))
      (node (ref "C514") (pin "2") (pinfunction "2_2") (pintype "passive"))
      (node (ref "C515") (pin "2") (pinfunction "2_2") (pintype "passive"))
      (node (ref "C516") (pin "1") (pinfunction "1_1") (pintype "passive"))
      (node (ref "C524") (pin "1") (pinfunction "1_1") (pintype "passive"))
      (node (ref "C525") (pin "1") (pinfunction "1_1") (pintype "passive"))
      (node (ref "L500") (pin "3") (pintype "passive"))
      (node (ref "R506") (pin "1") (pinfunction "1_1") (pintype "passive"))
      (node (ref "R524") (pin "1") (pinfunction "1_1") (pintype "passive"))
      (node (ref "R526") (pin "2") (pinfunction "2_2") (pintype "passive"))
      (node (ref "R527") (pin "2") (pinfunction "2_2") (pintype "passive"))
      (node (ref "R528") (pin "2") (pinfunction "2_2") (pintype "passive"))
      (node (ref "R529") (pin "2") (pinfunction "2_2") (pintype "passive"))
      (node (ref "T500") (pin "2") (pinfunction "Pri-_2") (pintype "passive"))
      (node (ref "U502") (pin "6") (pinfunction "GND_6") (pintype "passive"))
      (node (ref "U503") (pin "3") (pinfunction "4_3") (pintype "passive"))
    )
    (net (code "36") (name "Net-(T500-Sec1+)") (class "Default")
      (node (ref "C520") (pin "2") (pinfunction "2_2") (pintype "passive"))
      (node (ref "C521") (pin "2") (pinfunction "2_2") (pintype "passive"))
      (node (ref "F1") (pin "2") (pinfunction "2_2") (pintype "passive"))
      (node (ref "JP500") (pin "1") (pinfunction "1_1") (pintype "passive"))
      (node (ref "JP500") (pin "2") (pinfunction "2_2") (pintype "passive"))
      (node (ref "R525") (pin "2") (pinfunction "2_2") (pintype "passive"))
      (node (ref "T500") (pin "3") (pinfunction "Sec1+_3") (pintype "passive"))
    )
    (net (code "37") (name "Net-(U500-A)") (class "Default")
      (node (ref "JP502") (pin "3") (pinfunction "3_3") (pintype "passive"))
      (node (ref "R503") (pin "2") (pinfunction "2_2") (pintype "passive"))
      (node (ref "U500") (pin "12") (pinfunction "A_12") (pintype "passive"))
    )
    (net (code "38") (name "Net-(U500-B)") (class "Default")
      (node (ref "JP502") (pin "4") (pinfunction "4_4") (pintype "passive"))
      (node (ref "R503") (pin "1") (pinfunction "1_1") (pintype "passive"))
      (node (ref "U500") (pin "13") (pinfunction "B_13") (pintype "passive"))
    )
    (net (code "39") (name "Net-(U500-DE)") (class "Default")
      (node (ref "C526") (pin "2") (pinfunction "2_2") (pintype "passive"))
      (node (ref "U500") (pin "5") (pinfunction "DE_5") (pintype "passive"))
      (node (ref "X506") (pin "1") (pinfunction "1_1") (pintype "passive"))
    )
    (net (code "40") (name "Net-(U500-PV)") (class "Default")
      (node (ref "C27") (pin "1") (pinfunction "1_1") (pintype "passive"))
      (node (ref "JP501") (pin "5") (pinfunction "5_5") (pintype "passive"))
      (node (ref "L501") (pin "1") (pinfunction "1_1") (pintype "passive"))
      (node (ref "R507") (pin "1") (pinfunction "1_1") (pintype "passive"))
      (node (ref "U500") (pin "1") (pinfunction "Vcc1_1") (pintype "passive"))
      (node (ref "U500") (pin "7") (pinfunction "PV_7") (pintype "passive"))
      (node (ref "U504") (pin "3") (pinfunction "IN_3") (pintype "power_in"))
      (node (ref "U505") (pin "1") (pinfunction "Vcc1_1") (pintype "passive"))
      (node (ref "U505") (pin "7") (pinfunction "PV_7") (pintype "passive"))
    )
    (net (code "41") (name "Net-(U500-RXD)") (class "Default")
      (node (ref "U500") (pin "3") (pinfunction "RXD_3") (pintype "passive"))
      (node (ref "X504") (pin "1") (pinfunction "1_1") (pintype "passive"))
    )
    (net (code "42") (name "Net-(U500-TXD)") (class "Default")
      (node (ref "U500") (pin "6") (pinfunction "TXD_6") (pintype "passive"))
      (node (ref "X505") (pin "1") (pinfunction "1_1") (pintype "passive"))
    )
    (net (code "43") (name "Net-(U500-Vcc2)") (class "Default")
      (node (ref "C531") (pin "2") (pinfunction "2_2") (pintype "passive"))
      (node (ref "U500") (pin "16") (pinfunction "Vcc2_16") (pintype "passive"))
      (node (ref "U507") (pin "2") (pinfunction "OUT_2") (pintype "power_in"))
      (node (ref "U507") (pin "4") (pinfunction "OUT_4") (pintype "power_in"))
    )
    (net (code "44") (name "Net-(U501-OUT)") (class "Default")
      (node (ref "C507") (pin "2") (pinfunction "2_2") (pintype "passive"))
      (node (ref "JP501") (pin "8") (pinfunction "8_8") (pintype "passive"))
      (node (ref "U501") (pin "1") (pinfunction "OUT_1") (pintype "power_in"))
    )
    (net (code "45") (name "Net-(U502-COMP)") (class "Default")
      (node (ref "C513") (pin "2") (pinfunction "2_2") (pintype "passive"))
      (node (ref "C516") (pin "2") (pinfunction "2_2") (pintype "passive"))
      (node (ref "R513") (pin "1") (pinfunction "1_1") (pintype "passive"))
      (node (ref "U502") (pin "2") (pinfunction "COMP_2") (pintype "passive"))
      (node (ref "U503") (pin "4") (pinfunction "2_4") (pintype "passive"))
    )
    (net (code "46") (name "Net-(U502-CS)") (class "Default")
      (node (ref "C515") (pin "1") (pinfunction "1_1") (pintype "passive"))
      (node (ref "R523") (pin "2") (pinfunction "2_2") (pintype "passive"))
      (node (ref "U502") (pin "4") (pinfunction "CS_4") (pintype "passive"))
    )
    (net (code "47") (name "Net-(U502-GD)") (class "Default")
      (node (ref "R522") (pin "2") (pinfunction "2_2") (pintype "passive"))
      (node (ref "U502") (pin "7") (pinfunction "GD_7") (pintype "passive"))
    )
    (net (code "48") (name "Net-(U502-INV)") (class "Default")
      (node (ref "C513") (pin "1") (pinfunction "1_1") (pintype "passive"))
      (node (ref "R502") (pin "1") (pinfunction "1_1") (pintype "passive"))
      (node (ref "R506") (pin "2") (pinfunction "2_2") (pintype "passive"))
      (node (ref "R513") (pin "2") (pinfunction "2_2") (pintype "passive"))
      (node (ref "U502") (pin "1") (pinfunction "INV_1") (pintype "passive"))
    )
    (net (code "49") (name "Net-(U502-UFF)") (class "Default")
      (node (ref "C514") (pin "1") (pinfunction "1_1") (pintype "passive"))
      (node (ref "R500") (pin "1") (pinfunction "1_1") (pintype "passive"))
      (node (ref "R524") (pin "2") (pinfunction "2_2") (pintype "passive"))
      (node (ref "U502") (pin "3") (pinfunction "UFF_3") (pintype "passive"))
    )
    (net (code "50") (name "Net-(U502-ZCD)") (class "Default")
      (node (ref "R521") (pin "2") (pinfunction "2_2") (pintype "passive"))
      (node (ref "U502") (pin "5") (pinfunction "ZCD_5") (pintype "passive"))
    )
    (net (code "51") (name "Net-(U503-1)") (class "Default")
      (node (ref "R530") (pin "2") (pinfunction "2_2") (pintype "passive"))
      (node (ref "U503") (pin "2") (pinfunction "1_2") (pintype "passive"))
    )
    (net (code "52") (name "Net-(U505-A)") (class "Default")
      (node (ref "JP502") (pin "1") (pinfunction "1_1") (pintype "passive"))
      (node (ref "R501") (pin "2") (pinfunction "2_2") (pintype "passive"))
      (node (ref "U505") (pin "12") (pinfunction "A_12") (pintype "passive"))
    )
    (net (code "53") (name "Net-(U505-B)") (class "Default")
      (node (ref "JP502") (pin "2") (pinfunction "2_2") (pintype "passive"))
      (node (ref "R501") (pin "1") (pinfunction "1_1") (pintype "passive"))
      (node (ref "U505") (pin "13") (pinfunction "B_13") (pintype "passive"))
    )
    (net (code "54") (name "Net-(U505-DE)") (class "Default")
      (node (ref "C518") (pin "2") (pinfunction "2_2") (pintype "passive"))
      (node (ref "JP501") (pin "4") (pinfunction "4_4") (pintype "passive"))
      (node (ref "U505") (pin "5") (pinfunction "DE_5") (pintype "passive"))
    )
    (net (code "55") (name "Net-(U505-RXD)") (class "Default")
      (node (ref "JP501") (pin "9") (pinfunction "9_9") (pintype "passive"))
      (node (ref "U505") (pin "3") (pinfunction "RXD_3") (pintype "passive"))
    )
    (net (code "56") (name "Net-(U505-TXD)") (class "Default")
      (node (ref "JP501") (pin "10") (pinfunction "10_10") (pintype "passive"))
      (node (ref "U505") (pin "6") (pinfunction "TXD_6") (pintype "passive"))
    )
    (net (code "57") (name "Net-(U505-Vcc2)") (class "Default")
      (node (ref "C528") (pin "2") (pinfunction "2_2") (pintype "passive"))
      (node (ref "U505") (pin "16") (pinfunction "Vcc2_16") (pintype "passive"))
      (node (ref "U506") (pin "2") (pinfunction "OUT_2") (pintype "power_in"))
      (node (ref "U506") (pin "4") (pinfunction "OUT_4") (pintype "power_in"))
    )
    (net (code "58") (name "Net-(U506-GND)") (class "Default")
      (node (ref "C503") (pin "1") (pinfunction "1_1") (pintype "passive"))
      (node (ref "C519") (pin "1") (pinfunction "1_1") (pintype "passive"))
      (node (ref "C527") (pin "1") (pinfunction "1_1") (pintype "passive"))
      (node (ref "C528") (pin "1") (pinfunction "1_1") (pintype "passive"))
      (node (ref "U505") (pin "15") (pinfunction "Vdd2_15") (pintype "passive"))
      (node (ref "U505") (pin "9") (pinfunction "Vdd2_9") (pintype "passive"))
      (node (ref "U506") (pin "1") (pinfunction "GND_1") (pintype "power_in"))
      (node (ref "X501") (pin "1") (pinfunction "1_1") (pintype "passive"))
    )
    (net (code "59") (name "Net-(U507-GND)") (class "Default")
      (node (ref "C502") (pin "1") (pinfunction "1_1") (pintype "passive"))
      (node (ref "C529") (pin "1") (pinfunction "1_1") (pintype "passive"))
      (node (ref "C530") (pin "1") (pinfunction "1_1") (pintype "passive"))
      (node (ref "C531") (pin "1") (pinfunction "1_1") (pintype "passive"))
      (node (ref "U500") (pin "15") (pinfunction "Vdd2_15") (pintype "passive"))
      (node (ref "U500") (pin "9") (pinfunction "Vdd2_9") (pintype "passive"))
      (node (ref "U507") (pin "1") (pinfunction "GND_1") (pintype "power_in"))
      (node (ref "X503") (pin "1") (pinfunction "1_1") (pintype "passive"))
    )
    (net (code "60") (name "unconnected-(D511-NC-Pad4)") (class "Default")
      (node (ref "D511") (pin "4") (pinfunction "NC_4") (pintype "passive"))
    )
    (net (code "61") (name "unconnected-(D511-NC-Pad5)") (class "Default")
      (node (ref "D511") (pin "5") (pinfunction "NC_5") (pintype "passive"))
    )
    (net (code "62") (name "unconnected-(JP500-Pad3)") (class "Default")
      (node (ref "JP500") (pin "3") (pinfunction "3_3") (pintype "passive"))
    )
    (net (code "63") (name "unconnected-(JP500-Pad4)") (class "Default")
      (node (ref "JP500") (pin "4") (pinfunction "4_4") (pintype "passive"))
    )
    (net (code "64") (name "unconnected-(JP500-Pad5)") (class "Default")
      (node (ref "JP500") (pin "5") (pinfunction "5_5") (pintype "passive"))
    )
    (net (code "65") (name "unconnected-(JP500-Pad6)") (class "Default")
      (node (ref "JP500") (pin "6") (pinfunction "6_6") (pintype "passive"))
    )
    (net (code "66") (name "unconnected-(JP500-Pad7)") (class "Default")
      (node (ref "JP500") (pin "7") (pinfunction "7_7") (pintype "passive"))
    )
    (net (code "67") (name "unconnected-(JP500-Pad8)") (class "Default")
      (node (ref "JP500") (pin "8") (pinfunction "8_8") (pintype "passive"))
    )
    (net (code "68") (name "unconnected-(L500-Pad9)") (class "Default")
      (node (ref "L500") (pin "9") (pintype "passive"))
    )
    (net (code "69") (name "unconnected-(L500-Pad10)") (class "Default")
      (node (ref "L500") (pin "10") (pinfunction "10_10") (pintype "passive"))
    )
    (net (code "70") (name "unconnected-(U501-NC-Pad4)") (class "Default")
      (node (ref "U501") (pin "4") (pinfunction "NC_4") (pintype "passive"))
    )
    (net (code "71") (name "unconnected-(U501-NC-Pad8)") (class "Default")
      (node (ref "U501") (pin "8") (pinfunction "NC_8") (pintype "passive"))
    )
    (net (code "72") (name "unconnected-(X507-Pad1)") (class "Default")
      (node (ref "X507") (pin "1") (pinfunction "1_1") (pintype "passive"))
    )
  )
)
